# Decoup_Cap_2.net
KiCad netlist of a schematic drawn in Altium Designer
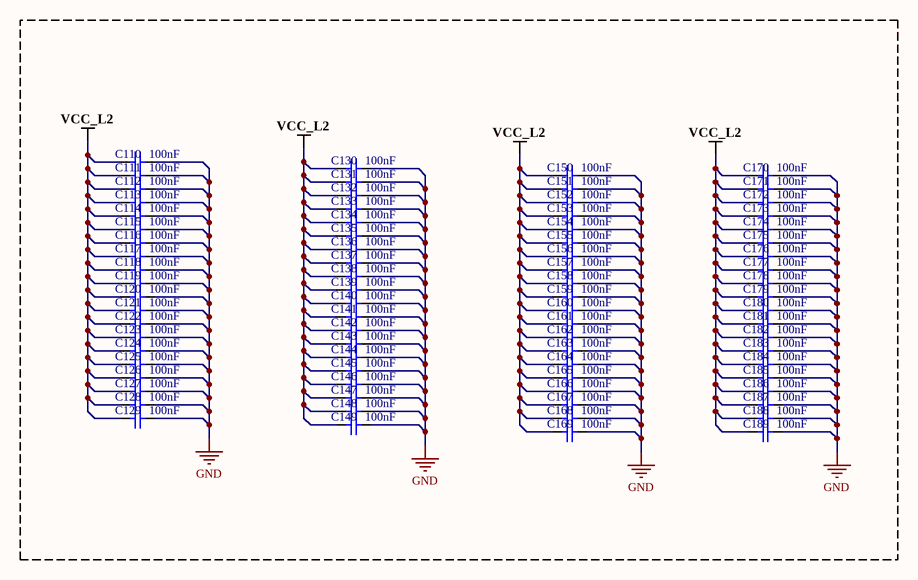
[diagram p0: Decoup_Cap 2.SchDoc]

(export (version "E")
  (design (tool "Eeschema 10.0.6"))
  (components
    (comp (ref "C110")
      (value "100nF")
      (footprint "Cap0402")
      (description "CAP CER 0.1UF 25V X7R 0402")
      (fields
        (field (name "MANUFACTURER") "Yageo")
        (field (name "MANUFACTURER PART NUMBER") "CC0402KRX7R8BB104")
      )
      (libsource (lib "TT_IntLib") (part "CC0402KRX7R8BB104"))
    )
    (comp (ref "C111")
      (value "100nF")
      (footprint "Cap0402")
      (description "CAP CER 0.1UF 25V X7R 0402")
      (fields
        (field (name "MANUFACTURER") "Yageo")
        (field (name "MANUFACTURER PART NUMBER") "CC0402KRX7R8BB104")
      )
      (libsource (lib "TT_IntLib") (part "CC0402KRX7R8BB104"))
    )
    (comp (ref "C112")
      (value "100nF")
      (footprint "Cap0402")
      (description "CAP CER 0.1UF 25V X7R 0402")
      (fields
        (field (name "MANUFACTURER") "Yageo")
        (field (name "MANUFACTURER PART NUMBER") "CC0402KRX7R8BB104")
      )
      (libsource (lib "TT_IntLib") (part "CC0402KRX7R8BB104"))
    )
    (comp (ref "C113")
      (value "100nF")
      (footprint "Cap0402")
      (description "CAP CER 0.1UF 25V X7R 0402")
      (fields
        (field (name "MANUFACTURER") "Yageo")
        (field (name "MANUFACTURER PART NUMBER") "CC0402KRX7R8BB104")
      )
      (libsource (lib "TT_IntLib") (part "CC0402KRX7R8BB104"))
    )
    (comp (ref "C114")
      (value "100nF")
      (footprint "Cap0402")
      (description "CAP CER 0.1UF 25V X7R 0402")
      (fields
        (field (name "MANUFACTURER") "Yageo")
        (field (name "MANUFACTURER PART NUMBER") "CC0402KRX7R8BB104")
      )
      (libsource (lib "TT_IntLib") (part "CC0402KRX7R8BB104"))
    )
    (comp (ref "C115")
      (value "100nF")
      (footprint "Cap0402")
      (description "CAP CER 0.1UF 25V X7R 0402")
      (fields
        (field (name "MANUFACTURER") "Yageo")
        (field (name "MANUFACTURER PART NUMBER") "CC0402KRX7R8BB104")
      )
      (libsource (lib "TT_IntLib") (part "CC0402KRX7R8BB104"))
    )
    (comp (ref "C116")
      (value "100nF")
      (footprint "Cap0402")
      (description "CAP CER 0.1UF 25V X7R 0402")
      (fields
        (field (name "MANUFACTURER") "Yageo")
        (field (name "MANUFACTURER PART NUMBER") "CC0402KRX7R8BB104")
      )
      (libsource (lib "TT_IntLib") (part "CC0402KRX7R8BB104"))
    )
    (comp (ref "C117")
      (value "100nF")
      (footprint "Cap0402")
      (description "CAP CER 0.1UF 25V X7R 0402")
      (fields
        (field (name "MANUFACTURER") "Yageo")
        (field (name "MANUFACTURER PART NUMBER") "CC0402KRX7R8BB104")
      )
      (libsource (lib "TT_IntLib") (part "CC0402KRX7R8BB104"))
    )
    (comp (ref "C118")
      (value "100nF")
      (footprint "Cap0402")
      (description "CAP CER 0.1UF 25V X7R 0402")
      (fields
        (field (name "MANUFACTURER") "Yageo")
        (field (name "MANUFACTURER PART NUMBER") "CC0402KRX7R8BB104")
      )
      (libsource (lib "TT_IntLib") (part "CC0402KRX7R8BB104"))
    )
    (comp (ref "C119")
      (value "100nF")
      (footprint "Cap0402")
      (description "CAP CER 0.1UF 25V X7R 0402")
      (fields
        (field (name "MANUFACTURER") "Yageo")
        (field (name "MANUFACTURER PART NUMBER") "CC0402KRX7R8BB104")
      )
      (libsource (lib "TT_IntLib") (part "CC0402KRX7R8BB104"))
    )
    (comp (ref "C120")
      (value "100nF")
      (footprint "Cap0402")
      (description "CAP CER 0.1UF 25V X7R 0402")
      (fields
        (field (name "MANUFACTURER") "Yageo")
        (field (name "MANUFACTURER PART NUMBER") "CC0402KRX7R8BB104")
      )
      (libsource (lib "TT_IntLib") (part "CC0402KRX7R8BB104"))
    )
    (comp (ref "C121")
      (value "100nF")
      (footprint "Cap0402")
      (description "CAP CER 0.1UF 25V X7R 0402")
      (fields
        (field (name "MANUFACTURER") "Yageo")
        (field (name "MANUFACTURER PART NUMBER") "CC0402KRX7R8BB104")
      )
      (libsource (lib "TT_IntLib") (part "CC0402KRX7R8BB104"))
    )
    (comp (ref "C122")
      (value "100nF")
      (footprint "Cap0402")
      (description "CAP CER 0.1UF 25V X7R 0402")
      (fields
        (field (name "MANUFACTURER") "Yageo")
        (field (name "MANUFACTURER PART NUMBER") "CC0402KRX7R8BB104")
      )
      (libsource (lib "TT_IntLib") (part "CC0402KRX7R8BB104"))
    )
    (comp (ref "C123")
      (value "100nF")
      (footprint "Cap0402")
      (description "CAP CER 0.1UF 25V X7R 0402")
      (fields
        (field (name "MANUFACTURER") "Yageo")
        (field (name "MANUFACTURER PART NUMBER") "CC0402KRX7R8BB104")
      )
      (libsource (lib "TT_IntLib") (part "CC0402KRX7R8BB104"))
    )
    (comp (ref "C124")
      (value "100nF")
      (footprint "Cap0402")
      (description "CAP CER 0.1UF 25V X7R 0402")
      (fields
        (field (name "MANUFACTURER") "Yageo")
        (field (name "MANUFACTURER PART NUMBER") "CC0402KRX7R8BB104")
      )
      (libsource (lib "TT_IntLib") (part "CC0402KRX7R8BB104"))
    )
    (comp (ref "C125")
      (value "100nF")
      (footprint "Cap0402")
      (description "CAP CER 0.1UF 25V X7R 0402")
      (fields
        (field (name "MANUFACTURER") "Yageo")
        (field (name "MANUFACTURER PART NUMBER") "CC0402KRX7R8BB104")
      )
      (libsource (lib "TT_IntLib") (part "CC0402KRX7R8BB104"))
    )
    (comp (ref "C126")
      (value "100nF")
      (footprint "Cap0402")
      (description "CAP CER 0.1UF 25V X7R 0402")
      (fields
        (field (name "MANUFACTURER") "Yageo")
        (field (name "MANUFACTURER PART NUMBER") "CC0402KRX7R8BB104")
      )
      (libsource (lib "TT_IntLib") (part "CC0402KRX7R8BB104"))
    )
    (comp (ref "C127")
      (value "100nF")
      (footprint "Cap0402")
      (description "CAP CER 0.1UF 25V X7R 0402")
      (fields
        (field (name "MANUFACTURER") "Yageo")
        (field (name "MANUFACTURER PART NUMBER") "CC0402KRX7R8BB104")
      )
      (libsource (lib "TT_IntLib") (part "CC0402KRX7R8BB104"))
    )
    (comp (ref "C128")
      (value "100nF")
      (footprint "Cap0402")
      (description "CAP CER 0.1UF 25V X7R 0402")
      (fields
        (field (name "MANUFACTURER") "Yageo")
        (field (name "MANUFACTURER PART NUMBER") "CC0402KRX7R8BB104")
      )
      (libsource (lib "TT_IntLib") (part "CC0402KRX7R8BB104"))
    )
    (comp (ref "C129")
      (value "100nF")
      (footprint "Cap0402")
      (description "CAP CER 0.1UF 25V X7R 0402")
      (fields
        (field (name "MANUFACTURER") "Yageo")
        (field (name "MANUFACTURER PART NUMBER") "CC0402KRX7R8BB104")
      )
      (libsource (lib "TT_IntLib") (part "CC0402KRX7R8BB104"))
    )
    (comp (ref "C130")
      (value "100nF")
      (footprint "Cap0402")
      (description "CAP CER 0.1UF 25V X7R 0402")
      (fields
        (field (name "MANUFACTURER") "Yageo")
        (field (name "MANUFACTURER PART NUMBER") "CC0402KRX7R8BB104")
      )
      (libsource (lib "TT_IntLib") (part "CC0402KRX7R8BB104"))
    )
    (comp (ref "C131")
      (value "100nF")
      (footprint "Cap0402")
      (description "CAP CER 0.1UF 25V X7R 0402")
      (fields
        (field (name "MANUFACTURER") "Yageo")
        (field (name "MANUFACTURER PART NUMBER") "CC0402KRX7R8BB104")
      )
      (libsource (lib "TT_IntLib") (part "CC0402KRX7R8BB104"))
    )
    (comp (ref "C132")
      (value "100nF")
      (footprint "Cap0402")
      (description "CAP CER 0.1UF 25V X7R 0402")
      (fields
        (field (name "MANUFACTURER") "Yageo")
        (field (name "MANUFACTURER PART NUMBER") "CC0402KRX7R8BB104")
      )
      (libsource (lib "TT_IntLib") (part "CC0402KRX7R8BB104"))
    )
    (comp (ref "C133")
      (value "100nF")
      (footprint "Cap0402")
      (description "CAP CER 0.1UF 25V X7R 0402")
      (fields
        (field (name "MANUFACTURER") "Yageo")
        (field (name "MANUFACTURER PART NUMBER") "CC0402KRX7R8BB104")
      )
      (libsource (lib "TT_IntLib") (part "CC0402KRX7R8BB104"))
    )
    (comp (ref "C134")
      (value "100nF")
      (footprint "Cap0402")
      (description "CAP CER 0.1UF 25V X7R 0402")
      (fields
        (field (name "MANUFACTURER") "Yageo")
        (field (name "MANUFACTURER PART NUMBER") "CC0402KRX7R8BB104")
      )
      (libsource (lib "TT_IntLib") (part "CC0402KRX7R8BB104"))
    )
    (comp (ref "C135")
      (value "100nF")
      (footprint "Cap0402")
      (description "CAP CER 0.1UF 25V X7R 0402")
      (fields
        (field (name "MANUFACTURER") "Yageo")
        (field (name "MANUFACTURER PART NUMBER") "CC0402KRX7R8BB104")
      )
      (libsource (lib "TT_IntLib") (part "CC0402KRX7R8BB104"))
    )
    (comp (ref "C136")
      (value "100nF")
      (footprint "Cap0402")
      (description "CAP CER 0.1UF 25V X7R 0402")
      (fields
        (field (name "MANUFACTURER") "Yageo")
        (field (name "MANUFACTURER PART NUMBER") "CC0402KRX7R8BB104")
      )
      (libsource (lib "TT_IntLib") (part "CC0402KRX7R8BB104"))
    )
    (comp (ref "C137")
      (value "100nF")
      (footprint "Cap0402")
      (description "CAP CER 0.1UF 25V X7R 0402")
      (fields
        (field (name "MANUFACTURER") "Yageo")
        (field (name "MANUFACTURER PART NUMBER") "CC0402KRX7R8BB104")
      )
      (libsource (lib "TT_IntLib") (part "CC0402KRX7R8BB104"))
    )
    (comp (ref "C138")
      (value "100nF")
      (footprint "Cap0402")
      (description "CAP CER 0.1UF 25V X7R 0402")
      (fields
        (field (name "MANUFACTURER") "Yageo")
        (field (name "MANUFACTURER PART NUMBER") "CC0402KRX7R8BB104")
      )
      (libsource (lib "TT_IntLib") (part "CC0402KRX7R8BB104"))
    )
    (comp (ref "C139")
      (value "100nF")
      (footprint "Cap0402")
      (description "CAP CER 0.1UF 25V X7R 0402")
      (fields
        (field (name "MANUFACTURER") "Yageo")
        (field (name "MANUFACTURER PART NUMBER") "CC0402KRX7R8BB104")
      )
      (libsource (lib "TT_IntLib") (part "CC0402KRX7R8BB104"))
    )
    (comp (ref "C140")
      (value "100nF")
      (footprint "Cap0402")
      (description "CAP CER 0.1UF 25V X7R 0402")
      (fields
        (field (name "MANUFACTURER") "Yageo")
        (field (name "MANUFACTURER PART NUMBER") "CC0402KRX7R8BB104")
      )
      (libsource (lib "TT_IntLib") (part "CC0402KRX7R8BB104"))
    )
    (comp (ref "C141")
      (value "100nF")
      (footprint "Cap0402")
      (description "CAP CER 0.1UF 25V X7R 0402")
      (fields
        (field (name "MANUFACTURER") "Yageo")
        (field (name "MANUFACTURER PART NUMBER") "CC0402KRX7R8BB104")
      )
      (libsource (lib "TT_IntLib") (part "CC0402KRX7R8BB104"))
    )
    (comp (ref "C142")
      (value "100nF")
      (footprint "Cap0402")
      (description "CAP CER 0.1UF 25V X7R 0402")
      (fields
        (field (name "MANUFACTURER") "Yageo")
        (field (name "MANUFACTURER PART NUMBER") "CC0402KRX7R8BB104")
      )
      (libsource (lib "TT_IntLib") (part "CC0402KRX7R8BB104"))
    )
    (comp (ref "C143")
      (value "100nF")
      (footprint "Cap0402")
      (description "CAP CER 0.1UF 25V X7R 0402")
      (fields
        (field (name "MANUFACTURER") "Yageo")
        (field (name "MANUFACTURER PART NUMBER") "CC0402KRX7R8BB104")
      )
      (libsource (lib "TT_IntLib") (part "CC0402KRX7R8BB104"))
    )
    (comp (ref "C144")
      (value "100nF")
      (footprint "Cap0402")
      (description "CAP CER 0.1UF 25V X7R 0402")
      (fields
        (field (name "MANUFACTURER") "Yageo")
        (field (name "MANUFACTURER PART NUMBER") "CC0402KRX7R8BB104")
      )
      (libsource (lib "TT_IntLib") (part "CC0402KRX7R8BB104"))
    )
    (comp (ref "C145")
      (value "100nF")
      (footprint "Cap0402")
      (description "CAP CER 0.1UF 25V X7R 0402")
      (fields
        (field (name "MANUFACTURER") "Yageo")
        (field (name "MANUFACTURER PART NUMBER") "CC0402KRX7R8BB104")
      )
      (libsource (lib "TT_IntLib") (part "CC0402KRX7R8BB104"))
    )
    (comp (ref "C146")
      (value "100nF")
      (footprint "Cap0402")
      (description "CAP CER 0.1UF 25V X7R 0402")
      (fields
        (field (name "MANUFACTURER") "Yageo")
        (field (name "MANUFACTURER PART NUMBER") "CC0402KRX7R8BB104")
      )
      (libsource (lib "TT_IntLib") (part "CC0402KRX7R8BB104"))
    )
    (comp (ref "C147")
      (value "100nF")
      (footprint "Cap0402")
      (description "CAP CER 0.1UF 25V X7R 0402")
      (fields
        (field (name "MANUFACTURER") "Yageo")
        (field (name "MANUFACTURER PART NUMBER") "CC0402KRX7R8BB104")
      )
      (libsource (lib "TT_IntLib") (part "CC0402KRX7R8BB104"))
    )
    (comp (ref "C148")
      (value "100nF")
      (footprint "Cap0402")
      (description "CAP CER 0.1UF 25V X7R 0402")
      (fields
        (field (name "MANUFACTURER") "Yageo")
        (field (name "MANUFACTURER PART NUMBER") "CC0402KRX7R8BB104")
      )
      (libsource (lib "TT_IntLib") (part "CC0402KRX7R8BB104"))
    )
    (comp (ref "C149")
      (value "100nF")
      (footprint "Cap0402")
      (description "CAP CER 0.1UF 25V X7R 0402")
      (fields
        (field (name "MANUFACTURER") "Yageo")
        (field (name "MANUFACTURER PART NUMBER") "CC0402KRX7R8BB104")
      )
      (libsource (lib "TT_IntLib") (part "CC0402KRX7R8BB104"))
    )
    (comp (ref "C150")
      (value "100nF")
      (footprint "Cap0402")
      (description "CAP CER 0.1UF 25V X7R 0402")
      (fields
        (field (name "MANUFACTURER") "Yageo")
        (field (name "MANUFACTURER PART NUMBER") "CC0402KRX7R8BB104")
      )
      (libsource (lib "TT_IntLib") (part "CC0402KRX7R8BB104"))
    )
    (comp (ref "C151")
      (value "100nF")
      (footprint "Cap0402")
      (description "CAP CER 0.1UF 25V X7R 0402")
      (fields
        (field (name "MANUFACTURER") "Yageo")
        (field (name "MANUFACTURER PART NUMBER") "CC0402KRX7R8BB104")
      )
      (libsource (lib "TT_IntLib") (part "CC0402KRX7R8BB104"))
    )
    (comp (ref "C152")
      (value "100nF")
      (footprint "Cap0402")
      (description "CAP CER 0.1UF 25V X7R 0402")
      (fields
        (field (name "MANUFACTURER") "Yageo")
        (field (name "MANUFACTURER PART NUMBER") "CC0402KRX7R8BB104")
      )
      (libsource (lib "TT_IntLib") (part "CC0402KRX7R8BB104"))
    )
    (comp (ref "C153")
      (value "100nF")
      (footprint "Cap0402")
      (description "CAP CER 0.1UF 25V X7R 0402")
      (fields
        (field (name "MANUFACTURER") "Yageo")
        (field (name "MANUFACTURER PART NUMBER") "CC0402KRX7R8BB104")
      )
      (libsource (lib "TT_IntLib") (part "CC0402KRX7R8BB104"))
    )
    (comp (ref "C154")
      (value "100nF")
      (footprint "Cap0402")
      (description "CAP CER 0.1UF 25V X7R 0402")
      (fields
        (field (name "MANUFACTURER") "Yageo")
        (field (name "MANUFACTURER PART NUMBER") "CC0402KRX7R8BB104")
      )
      (libsource (lib "TT_IntLib") (part "CC0402KRX7R8BB104"))
    )
    (comp (ref "C155")
      (value "100nF")
      (footprint "Cap0402")
      (description "CAP CER 0.1UF 25V X7R 0402")
      (fields
        (field (name "MANUFACTURER") "Yageo")
        (field (name "MANUFACTURER PART NUMBER") "CC0402KRX7R8BB104")
      )
      (libsource (lib "TT_IntLib") (part "CC0402KRX7R8BB104"))
    )
    (comp (ref "C156")
      (value "100nF")
      (footprint "Cap0402")
      (description "CAP CER 0.1UF 25V X7R 0402")
      (fields
        (field (name "MANUFACTURER") "Yageo")
        (field (name "MANUFACTURER PART NUMBER") "CC0402KRX7R8BB104")
      )
      (libsource (lib "TT_IntLib") (part "CC0402KRX7R8BB104"))
    )
    (comp (ref "C157")
      (value "100nF")
      (footprint "Cap0402")
      (description "CAP CER 0.1UF 25V X7R 0402")
      (fields
        (field (name "MANUFACTURER") "Yageo")
        (field (name "MANUFACTURER PART NUMBER") "CC0402KRX7R8BB104")
      )
      (libsource (lib "TT_IntLib") (part "CC0402KRX7R8BB104"))
    )
    (comp (ref "C158")
      (value "100nF")
      (footprint "Cap0402")
      (description "CAP CER 0.1UF 25V X7R 0402")
      (fields
        (field (name "MANUFACTURER") "Yageo")
        (field (name "MANUFACTURER PART NUMBER") "CC0402KRX7R8BB104")
      )
      (libsource (lib "TT_IntLib") (part "CC0402KRX7R8BB104"))
    )
    (comp (ref "C159")
      (value "100nF")
      (footprint "Cap0402")
      (description "CAP CER 0.1UF 25V X7R 0402")
      (fields
        (field (name "MANUFACTURER") "Yageo")
        (field (name "MANUFACTURER PART NUMBER") "CC0402KRX7R8BB104")
      )
      (libsource (lib "TT_IntLib") (part "CC0402KRX7R8BB104"))
    )
    (comp (ref "C160")
      (value "100nF")
      (footprint "Cap0402")
      (description "CAP CER 0.1UF 25V X7R 0402")
      (fields
        (field (name "MANUFACTURER") "Yageo")
        (field (name "MANUFACTURER PART NUMBER") "CC0402KRX7R8BB104")
      )
      (libsource (lib "TT_IntLib") (part "CC0402KRX7R8BB104"))
    )
    (comp (ref "C161")
      (value "100nF")
      (footprint "Cap0402")
      (description "CAP CER 0.1UF 25V X7R 0402")
      (fields
        (field (name "MANUFACTURER") "Yageo")
        (field (name "MANUFACTURER PART NUMBER") "CC0402KRX7R8BB104")
      )
      (libsource (lib "TT_IntLib") (part "CC0402KRX7R8BB104"))
    )
    (comp (ref "C162")
      (value "100nF")
      (footprint "Cap0402")
      (description "CAP CER 0.1UF 25V X7R 0402")
      (fields
        (field (name "MANUFACTURER") "Yageo")
        (field (name "MANUFACTURER PART NUMBER") "CC0402KRX7R8BB104")
      )
      (libsource (lib "TT_IntLib") (part "CC0402KRX7R8BB104"))
    )
    (comp (ref "C163")
      (value "100nF")
      (footprint "Cap0402")
      (description "CAP CER 0.1UF 25V X7R 0402")
      (fields
        (field (name "MANUFACTURER") "Yageo")
        (field (name "MANUFACTURER PART NUMBER") "CC0402KRX7R8BB104")
      )
      (libsource (lib "TT_IntLib") (part "CC0402KRX7R8BB104"))
    )
    (comp (ref "C164")
      (value "100nF")
      (footprint "Cap0402")
      (description "CAP CER 0.1UF 25V X7R 0402")
      (fields
        (field (name "MANUFACTURER") "Yageo")
        (field (name "MANUFACTURER PART NUMBER") "CC0402KRX7R8BB104")
      )
      (libsource (lib "TT_IntLib") (part "CC0402KRX7R8BB104"))
    )
    (comp (ref "C165")
      (value "100nF")
      (footprint "Cap0402")
      (description "CAP CER 0.1UF 25V X7R 0402")
      (fields
        (field (name "MANUFACTURER") "Yageo")
        (field (name "MANUFACTURER PART NUMBER") "CC0402KRX7R8BB104")
      )
      (libsource (lib "TT_IntLib") (part "CC0402KRX7R8BB104"))
    )
    (comp (ref "C166")
      (value "100nF")
      (footprint "Cap0402")
      (description "CAP CER 0.1UF 25V X7R 0402")
      (fields
        (field (name "MANUFACTURER") "Yageo")
        (field (name "MANUFACTURER PART NUMBER") "CC0402KRX7R8BB104")
      )
      (libsource (lib "TT_IntLib") (part "CC0402KRX7R8BB104"))
    )
    (comp (ref "C167")
      (value "100nF")
      (footprint "Cap0402")
      (description "CAP CER 0.1UF 25V X7R 0402")
      (fields
        (field (name "MANUFACTURER") "Yageo")
        (field (name "MANUFACTURER PART NUMBER") "CC0402KRX7R8BB104")
      )
      (libsource (lib "TT_IntLib") (part "CC0402KRX7R8BB104"))
    )
    (comp (ref "C168")
      (value "100nF")
      (footprint "Cap0402")
      (description "CAP CER 0.1UF 25V X7R 0402")
      (fields
        (field (name "MANUFACTURER") "Yageo")
        (field (name "MANUFACTURER PART NUMBER") "CC0402KRX7R8BB104")
      )
      (libsource (lib "TT_IntLib") (part "CC0402KRX7R8BB104"))
    )
    (comp (ref "C169")
      (value "100nF")
      (footprint "Cap0402")
      (description "CAP CER 0.1UF 25V X7R 0402")
      (fields
        (field (name "MANUFACTURER") "Yageo")
        (field (name "MANUFACTURER PART NUMBER") "CC0402KRX7R8BB104")
      )
      (libsource (lib "TT_IntLib") (part "CC0402KRX7R8BB104"))
    )
    (comp (ref "C170")
      (value "100nF")
      (footprint "Cap0402")
      (description "CAP CER 0.1UF 25V X7R 0402")
      (fields
        (field (name "MANUFACTURER") "Yageo")
        (field (name "MANUFACTURER PART NUMBER") "CC0402KRX7R8BB104")
      )
      (libsource (lib "TT_IntLib") (part "CC0402KRX7R8BB104"))
    )
    (comp (ref "C171")
      (value "100nF")
      (footprint "Cap0402")
      (description "CAP CER 0.1UF 25V X7R 0402")
      (fields
        (field (name "MANUFACTURER") "Yageo")
        (field (name "MANUFACTURER PART NUMBER") "CC0402KRX7R8BB104")
      )
      (libsource (lib "TT_IntLib") (part "CC0402KRX7R8BB104"))
    )
    (comp (ref "C172")
      (value "100nF")
      (footprint "Cap0402")
      (description "CAP CER 0.1UF 25V X7R 0402")
      (fields
        (field (name "MANUFACTURER") "Yageo")
        (field (name "MANUFACTURER PART NUMBER") "CC0402KRX7R8BB104")
      )
      (libsource (lib "TT_IntLib") (part "CC0402KRX7R8BB104"))
    )
    (comp (ref "C173")
      (value "100nF")
      (footprint "Cap0402")
      (description "CAP CER 0.1UF 25V X7R 0402")
      (fields
        (field (name "MANUFACTURER") "Yageo")
        (field (name "MANUFACTURER PART NUMBER") "CC0402KRX7R8BB104")
      )
      (libsource (lib "TT_IntLib") (part "CC0402KRX7R8BB104"))
    )
    (comp (ref "C174")
      (value "100nF")
      (footprint "Cap0402")
      (description "CAP CER 0.1UF 25V X7R 0402")
      (fields
        (field (name "MANUFACTURER") "Yageo")
        (field (name "MANUFACTURER PART NUMBER") "CC0402KRX7R8BB104")
      )
      (libsource (lib "TT_IntLib") (part "CC0402KRX7R8BB104"))
    )
    (comp (ref "C175")
      (value "100nF")
      (footprint "Cap0402")
      (description "CAP CER 0.1UF 25V X7R 0402")
      (fields
        (field (name "MANUFACTURER") "Yageo")
        (field (name "MANUFACTURER PART NUMBER") "CC0402KRX7R8BB104")
      )
      (libsource (lib "TT_IntLib") (part "CC0402KRX7R8BB104"))
    )
    (comp (ref "C176")
      (value "100nF")
      (footprint "Cap0402")
      (description "CAP CER 0.1UF 25V X7R 0402")
      (fields
        (field (name "MANUFACTURER") "Yageo")
        (field (name "MANUFACTURER PART NUMBER") "CC0402KRX7R8BB104")
      )
      (libsource (lib "TT_IntLib") (part "CC0402KRX7R8BB104"))
    )
    (comp (ref "C177")
      (value "100nF")
      (footprint "Cap0402")
      (description "CAP CER 0.1UF 25V X7R 0402")
      (fields
        (field (name "MANUFACTURER") "Yageo")
        (field (name "MANUFACTURER PART NUMBER") "CC0402KRX7R8BB104")
      )
      (libsource (lib "TT_IntLib") (part "CC0402KRX7R8BB104"))
    )
    (comp (ref "C178")
      (value "100nF")
      (footprint "Cap0402")
      (description "CAP CER 0.1UF 25V X7R 0402")
      (fields
        (field (name "MANUFACTURER") "Yageo")
        (field (name "MANUFACTURER PART NUMBER") "CC0402KRX7R8BB104")
      )
      (libsource (lib "TT_IntLib") (part "CC0402KRX7R8BB104"))
    )
    (comp (ref "C179")
      (value "100nF")
      (footprint "Cap0402")
      (description "CAP CER 0.1UF 25V X7R 0402")
      (fields
        (field (name "MANUFACTURER") "Yageo")
        (field (name "MANUFACTURER PART NUMBER") "CC0402KRX7R8BB104")
      )
      (libsource (lib "TT_IntLib") (part "CC0402KRX7R8BB104"))
    )
    (comp (ref "C180")
      (value "100nF")
      (footprint "Cap0402")
      (description "CAP CER 0.1UF 25V X7R 0402")
      (fields
        (field (name "MANUFACTURER") "Yageo")
        (field (name "MANUFACTURER PART NUMBER") "CC0402KRX7R8BB104")
      )
      (libsource (lib "TT_IntLib") (part "CC0402KRX7R8BB104"))
    )
    (comp (ref "C181")
      (value "100nF")
      (footprint "Cap0402")
      (description "CAP CER 0.1UF 25V X7R 0402")
      (fields
        (field (name "MANUFACTURER") "Yageo")
        (field (name "MANUFACTURER PART NUMBER") "CC0402KRX7R8BB104")
      )
      (libsource (lib "TT_IntLib") (part "CC0402KRX7R8BB104"))
    )
    (comp (ref "C182")
      (value "100nF")
      (footprint "Cap0402")
      (description "CAP CER 0.1UF 25V X7R 0402")
      (fields
        (field (name "MANUFACTURER") "Yageo")
        (field (name "MANUFACTURER PART NUMBER") "CC0402KRX7R8BB104")
      )
      (libsource (lib "TT_IntLib") (part "CC0402KRX7R8BB104"))
    )
    (comp (ref "C183")
      (value "100nF")
      (footprint "Cap0402")
      (description "CAP CER 0.1UF 25V X7R 0402")
      (fields
        (field (name "MANUFACTURER") "Yageo")
        (field (name "MANUFACTURER PART NUMBER") "CC0402KRX7R8BB104")
      )
      (libsource (lib "TT_IntLib") (part "CC0402KRX7R8BB104"))
    )
    (comp (ref "C184")
      (value "100nF")
      (footprint "Cap0402")
      (description "CAP CER 0.1UF 25V X7R 0402")
      (fields
        (field (name "MANUFACTURER") "Yageo")
        (field (name "MANUFACTURER PART NUMBER") "CC0402KRX7R8BB104")
      )
      (libsource (lib "TT_IntLib") (part "CC0402KRX7R8BB104"))
    )
    (comp (ref "C185")
      (value "100nF")
      (footprint "Cap0402")
      (description "CAP CER 0.1UF 25V X7R 0402")
      (fields
        (field (name "MANUFACTURER") "Yageo")
        (field (name "MANUFACTURER PART NUMBER") "CC0402KRX7R8BB104")
      )
      (libsource (lib "TT_IntLib") (part "CC0402KRX7R8BB104"))
    )
    (comp (ref "C186")
      (value "100nF")
      (footprint "Cap0402")
      (description "CAP CER 0.1UF 25V X7R 0402")
      (fields
        (field (name "MANUFACTURER") "Yageo")
        (field (name "MANUFACTURER PART NUMBER") "CC0402KRX7R8BB104")
      )
      (libsource (lib "TT_IntLib") (part "CC0402KRX7R8BB104"))
    )
    (comp (ref "C187")
      (value "100nF")
      (footprint "Cap0402")
      (description "CAP CER 0.1UF 25V X7R 0402")
      (fields
        (field (name "MANUFACTURER") "Yageo")
        (field (name "MANUFACTURER PART NUMBER") "CC0402KRX7R8BB104")
      )
      (libsource (lib "TT_IntLib") (part "CC0402KRX7R8BB104"))
    )
    (comp (ref "C188")
      (value "100nF")
      (footprint "Cap0402")
      (description "CAP CER 0.1UF 25V X7R 0402")
      (fields
        (field (name "MANUFACTURER") "Yageo")
        (field (name "MANUFACTURER PART NUMBER") "CC0402KRX7R8BB104")
      )
      (libsource (lib "TT_IntLib") (part "CC0402KRX7R8BB104"))
    )
    (comp (ref "C189")
      (value "100nF")
      (footprint "Cap0402")
      (description "CAP CER 0.1UF 25V X7R 0402")
      (fields
        (field (name "MANUFACTURER") "Yageo")
        (field (name "MANUFACTURER PART NUMBER") "CC0402KRX7R8BB104")
      )
      (libsource (lib "TT_IntLib") (part "CC0402KRX7R8BB104"))
    )
  )
  (nets
    (net (code "1") (name "GND") (class "Default")
      (node (ref "C110") (pin "1") (pintype "passive"))
      (node (ref "C111") (pin "1") (pintype "passive"))
      (node (ref "C112") (pin "1") (pintype "passive"))
      (node (ref "C113") (pin "1") (pintype "passive"))
      (node (ref "C114") (pin "1") (pintype "passive"))
      (node (ref "C115") (pin "1") (pintype "passive"))
      (node (ref "C116") (pin "1") (pintype "passive"))
      (node (ref "C117") (pin "1") (pintype "passive"))
      (node (ref "C118") (pin "1") (pintype "passive"))
      (node (ref "C119") (pin "1") (pintype "passive"))
      (node (ref "C120") (pin "1") (pintype "passive"))
      (node (ref "C121") (pin "1") (pintype "passive"))
      (node (ref "C122") (pin "1") (pintype "passive"))
      (node (ref "C123") (pin "1") (pintype "passive"))
      (node (ref "C124") (pin "1") (pintype "passive"))
      (node (ref "C125") (pin "1") (pintype "passive"))
      (node (ref "C126") (pin "1") (pintype "passive"))
      (node (ref "C127") (pin "1") (pintype "passive"))
      (node (ref "C128") (pin "1") (pintype "passive"))
      (node (ref "C129") (pin "1") (pintype "passive"))
      (node (ref "C130") (pin "1") (pintype "passive"))
      (node (ref "C131") (pin "1") (pintype "passive"))
      (node (ref "C132") (pin "1") (pintype "passive"))
      (node (ref "C133") (pin "1") (pintype "passive"))
      (node (ref "C134") (pin "1") (pintype "passive"))
      (node (ref "C135") (pin "1") (pintype "passive"))
      (node (ref "C136") (pin "1") (pintype "passive"))
      (node (ref "C137") (pin "1") (pintype "passive"))
      (node (ref "C138") (pin "1") (pintype "passive"))
      (node (ref "C139") (pin "1") (pintype "passive"))
      (node (ref "C140") (pin "1") (pintype "passive"))
      (node (ref "C141") (pin "1") (pintype "passive"))
      (node (ref "C142") (pin "1") (pintype "passive"))
      (node (ref "C143") (pin "1") (pintype "passive"))
      (node (ref "C144") (pin "1") (pintype "passive"))
      (node (ref "C145") (pin "1") (pintype "passive"))
      (node (ref "C146") (pin "1") (pintype "passive"))
      (node (ref "C147") (pin "1") (pintype "passive"))
      (node (ref "C148") (pin "1") (pintype "passive"))
      (node (ref "C149") (pin "1") (pintype "passive"))
      (node (ref "C150") (pin "1") (pintype "passive"))
      (node (ref "C151") (pin "1") (pintype "passive"))
      (node (ref "C152") (pin "1") (pintype "passive"))
      (node (ref "C153") (pin "1") (pintype "passive"))
      (node (ref "C154") (pin "1") (pintype "passive"))
      (node (ref "C155") (pin "1") (pintype "passive"))
      (node (ref "C156") (pin "1") (pintype "passive"))
      (node (ref "C157") (pin "1") (pintype "passive"))
      (node (ref "C158") (pin "1") (pintype "passive"))
      (node (ref "C159") (pin "1") (pintype "passive"))
      (node (ref "C160") (pin "1") (pintype "passive"))
      (node (ref "C161") (pin "1") (pintype "passive"))
      (node (ref "C162") (pin "1") (pintype "passive"))
      (node (ref "C163") (pin "1") (pintype "passive"))
      (node (ref "C164") (pin "1") (pintype "passive"))
      (node (ref "C165") (pin "1") (pintype "passive"))
      (node (ref "C166") (pin "1") (pintype "passive"))
      (node (ref "C167") (pin "1") (pintype "passive"))
      (node (ref "C168") (pin "1") (pintype "passive"))
      (node (ref "C169") (pin "1") (pintype "passive"))
      (node (ref "C170") (pin "1") (pintype "passive"))
      (node (ref "C171") (pin "1") (pintype "passive"))
      (node (ref "C172") (pin "1") (pintype "passive"))
      (node (ref "C173") (pin "1") (pintype "passive"))
      (node (ref "C174") (pin "1") (pintype "passive"))
      (node (ref "C175") (pin "1") (pintype "passive"))
      (node (ref "C176") (pin "1") (pintype "passive"))
      (node (ref "C177") (pin "1") (pintype "passive"))
      (node (ref "C178") (pin "1") (pintype "passive"))
      (node (ref "C179") (pin "1") (pintype "passive"))
      (node (ref "C180") (pin "1") (pintype "passive"))
      (node (ref "C181") (pin "1") (pintype "passive"))
      (node (ref "C182") (pin "1") (pintype "passive"))
      (node (ref "C183") (pin "1") (pintype "passive"))
      (node (ref "C184") (pin "1") (pintype "passive"))
      (node (ref "C185") (pin "1") (pintype "passive"))
      (node (ref "C186") (pin "1") (pintype "passive"))
      (node (ref "C187") (pin "1") (pintype "passive"))
      (node (ref "C188") (pin "1") (pintype "passive"))
      (node (ref "C189") (pin "1") (pintype "passive"))
    )
    (net (code "2") (name "VCC_L2") (class "Default")
      (node (ref "C110") (pin "2") (pintype "passive"))
      (node (ref "C111") (pin "2") (pintype "passive"))
      (node (ref "C112") (pin "2") (pintype "passive"))
      (node (ref "C113") (pin "2") (pintype "passive"))
      (node (ref "C114") (pin "2") (pintype "passive"))
      (node (ref "C115") (pin "2") (pintype "passive"))
      (node (ref "C116") (pin "2") (pintype "passive"))
      (node (ref "C117") (pin "2") (pintype "passive"))
      (node (ref "C118") (pin "2") (pintype "passive"))
      (node (ref "C119") (pin "2") (pintype "passive"))
      (node (ref "C120") (pin "2") (pintype "passive"))
      (node (ref "C121") (pin "2") (pintype "passive"))
      (node (ref "C122") (pin "2") (pintype "passive"))
      (node (ref "C123") (pin "2") (pintype "passive"))
      (node (ref "C124") (pin "2") (pintype "passive"))
      (node (ref "C125") (pin "2") (pintype "passive"))
      (node (ref "C126") (pin "2") (pintype "passive"))
      (node (ref "C127") (pin "2") (pintype "passive"))
      (node (ref "C128") (pin "2") (pintype "passive"))
      (node (ref "C129") (pin "2") (pintype "passive"))
      (node (ref "C130") (pin "2") (pintype "passive"))
      (node (ref "C131") (pin "2") (pintype "passive"))
      (node (ref "C132") (pin "2") (pintype "passive"))
      (node (ref "C133") (pin "2") (pintype "passive"))
      (node (ref "C134") (pin "2") (pintype "passive"))
      (node (ref "C135") (pin "2") (pintype "passive"))
      (node (ref "C136") (pin "2") (pintype "passive"))
      (node (ref "C137") (pin "2") (pintype "passive"))
      (node (ref "C138") (pin "2") (pintype "passive"))
      (node (ref "C139") (pin "2") (pintype "passive"))
      (node (ref "C140") (pin "2") (pintype "passive"))
      (node (ref "C141") (pin "2") (pintype "passive"))
      (node (ref "C142") (pin "2") (pintype "passive"))
      (node (ref "C143") (pin "2") (pintype "passive"))
      (node (ref "C144") (pin "2") (pintype "passive"))
      (node (ref "C145") (pin "2") (pintype "passive"))
      (node (ref "C146") (pin "2") (pintype "passive"))
      (node (ref "C147") (pin "2") (pintype "passive"))
      (node (ref "C148") (pin "2") (pintype "passive"))
      (node (ref "C149") (pin "2") (pintype "passive"))
      (node (ref "C150") (pin "2") (pintype "passive"))
      (node (ref "C151") (pin "2") (pintype "passive"))
      (node (ref "C152") (pin "2") (pintype "passive"))
      (node (ref "C153") (pin "2") (pintype "passive"))
      (node (ref "C154") (pin "2") (pintype "passive"))
      (node (ref "C155") (pin "2") (pintype "passive"))
      (node (ref "C156") (pin "2") (pintype "passive"))
      (node (ref "C157") (pin "2") (pintype "passive"))
      (node (ref "C158") (pin "2") (pintype "passive"))
      (node (ref "C159") (pin "2") (pintype "passive"))
      (node (ref "C160") (pin "2") (pintype "passive"))
      (node (ref "C161") (pin "2") (pintype "passive"))
      (node (ref "C162") (pin "2") (pintype "passive"))
      (node (ref "C163") (pin "2") (pintype "passive"))
      (node (ref "C164") (pin "2") (pintype "passive"))
      (node (ref "C165") (pin "2") (pintype "passive"))
      (node (ref "C166") (pin "2") (pintype "passive"))
      (node (ref "C167") (pin "2") (pintype "passive"))
      (node (ref "C168") (pin "2") (pintype "passive"))
      (node (ref "C169") (pin "2") (pintype "passive"))
      (node (ref "C170") (pin "2") (pintype "passive"))
      (node (ref "C171") (pin "2") (pintype "passive"))
      (node (ref "C172") (pin "2") (pintype "passive"))
      (node (ref "C173") (pin "2") (pintype "passive"))
      (node (ref "C174") (pin "2") (pintype "passive"))
      (node (ref "C175") (pin "2") (pintype "passive"))
      (node (ref "C176") (pin "2") (pintype "passive"))
      (node (ref "C177") (pin "2") (pintype "passive"))
      (node (ref "C178") (pin "2") (pintype "passive"))
      (node (ref "C179") (pin "2") (pintype "passive"))
      (node (ref "C180") (pin "2") (pintype "passive"))
      (node (ref "C181") (pin "2") (pintype "passive"))
      (node (ref "C182") (pin "2") (pintype "passive"))
      (node (ref "C183") (pin "2") (pintype "passive"))
      (node (ref "C184") (pin "2") (pintype "passive"))
      (node (ref "C185") (pin "2") (pintype "passive"))
      (node (ref "C186") (pin "2") (pintype "passive"))
      (node (ref "C187") (pin "2") (pintype "passive"))
      (node (ref "C188") (pin "2") (pintype "passive"))
      (node (ref "C189") (pin "2") (pintype "passive"))
    )
  )
)
